# v0_6_2.net
KiCad netlist of a schematic drawn in EAGLE
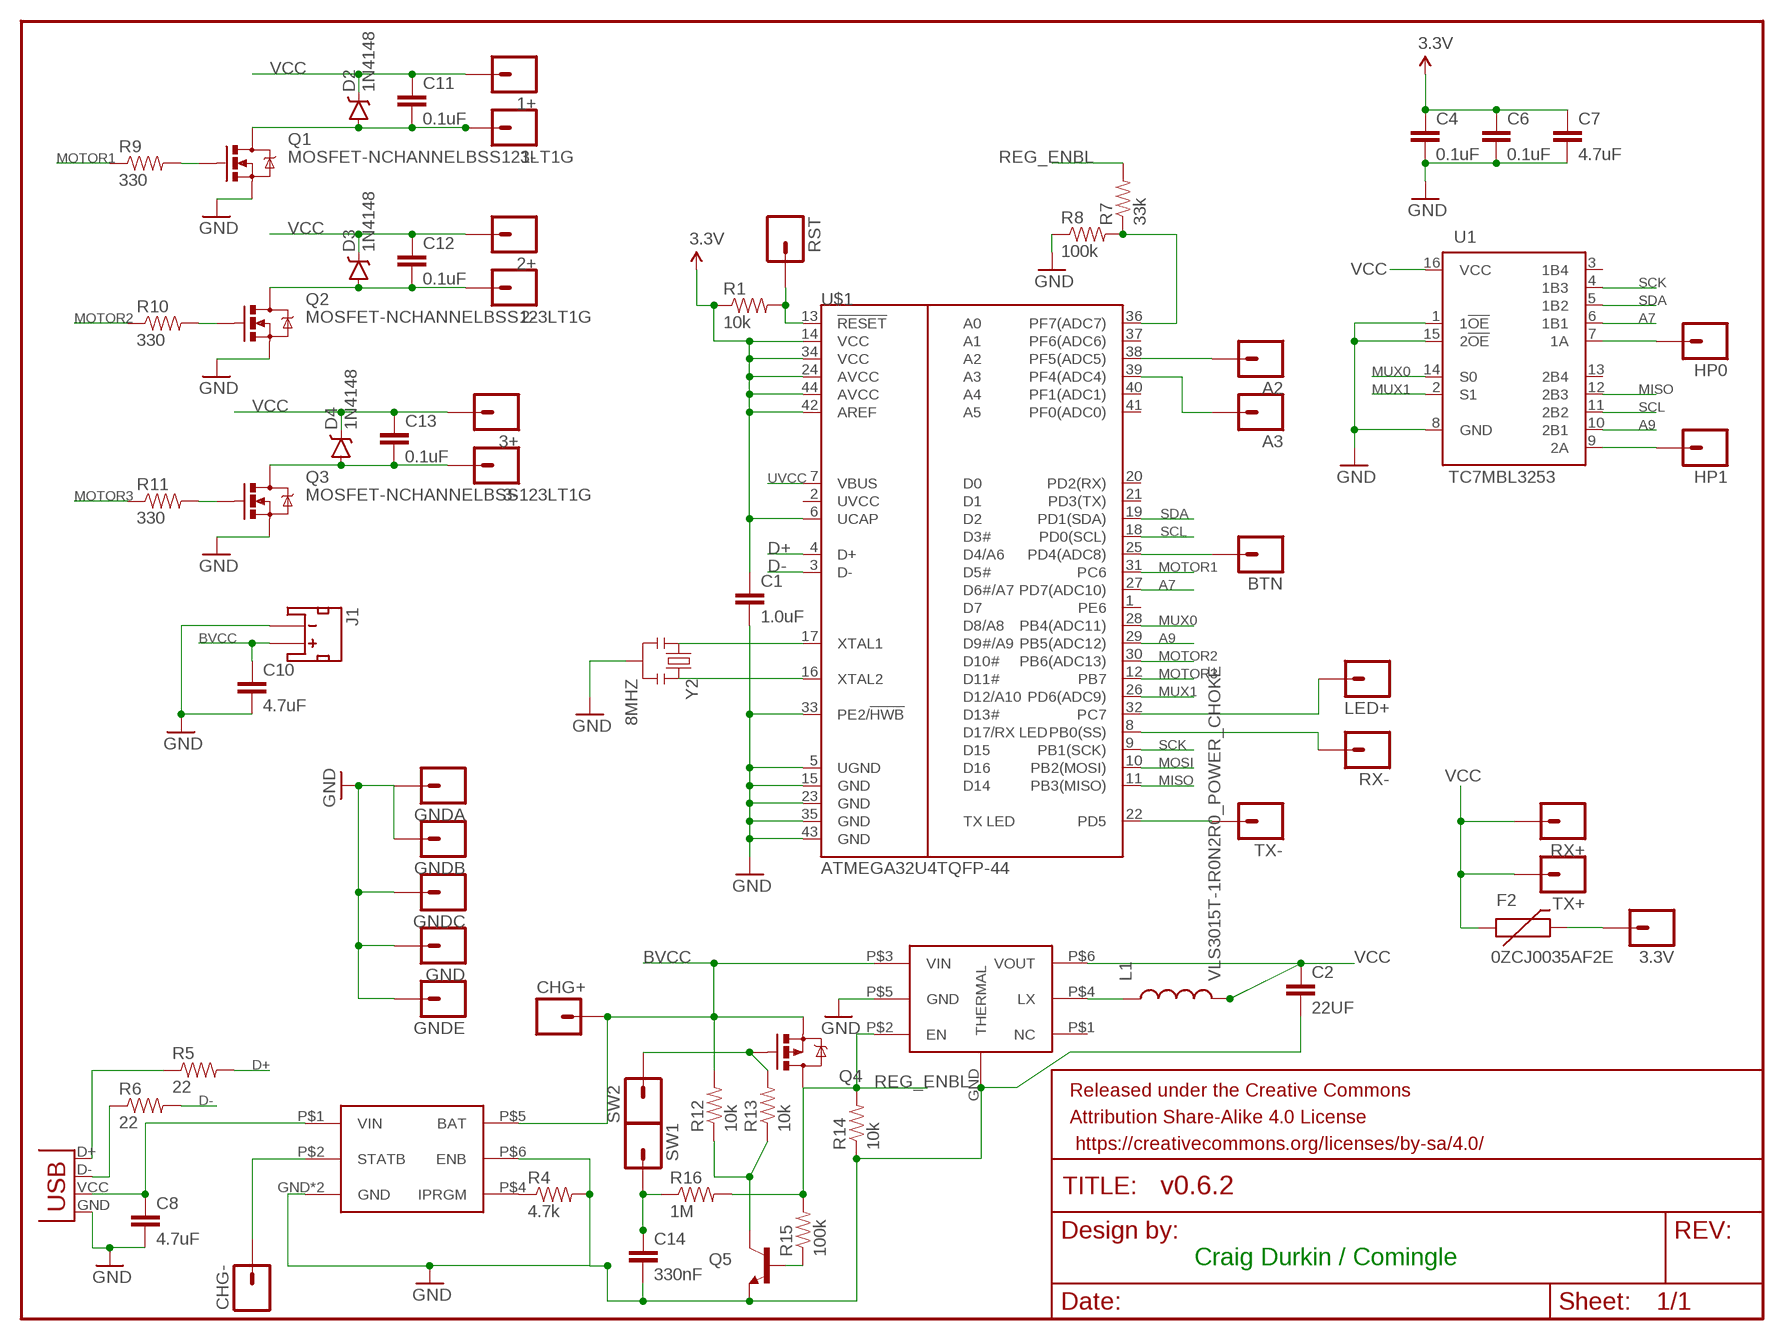
[diagram p0: schematic, sheet 1]

(export (version "E")
  (design (tool "Eeschema 10.0.6"))
  (components
    (comp (ref "1+")
      (value "M01PTH")
      (footprint "eagle-import:1X01")
      (libsource (lib "eagle-import") (part "M01PTH"))
    )
    (comp (ref "1-")
      (value "M01PTH")
      (footprint "eagle-import:1X01")
      (libsource (lib "eagle-import") (part "M01PTH"))
    )
    (comp (ref "2+")
      (value "M01PTH")
      (footprint "eagle-import:1X01")
      (libsource (lib "eagle-import") (part "M01PTH"))
    )
    (comp (ref "2-")
      (value "M01PTH")
      (footprint "eagle-import:1X01")
      (libsource (lib "eagle-import") (part "M01PTH"))
    )
    (comp (ref "3+")
      (value "M01PTH")
      (footprint "eagle-import:1X01")
      (libsource (lib "eagle-import") (part "M01PTH"))
    )
    (comp (ref "3-")
      (value "M01PTH")
      (footprint "eagle-import:1X01")
      (libsource (lib "eagle-import") (part "M01PTH"))
    )
    (comp (ref "3.3V")
      (value "M01PTH")
      (footprint "eagle-import:1X01")
      (libsource (lib "eagle-import") (part "M01PTH"))
    )
    (comp (ref "A2")
      (value "M01PTH")
      (footprint "eagle-import:1X01")
      (libsource (lib "eagle-import") (part "M01PTH"))
    )
    (comp (ref "A3")
      (value "M01PTH")
      (footprint "eagle-import:1X01")
      (libsource (lib "eagle-import") (part "M01PTH"))
    )
    (comp (ref "BTN")
      (value "M01PTH")
      (footprint "eagle-import:1X01")
      (libsource (lib "eagle-import") (part "M01PTH"))
    )
    (comp (ref "C1")
      (value "1.0uF")
      (footprint "eagle-import:0603-CAP")
      (libsource (lib "eagle-import") (part "CAP0603-CAP"))
    )
    (comp (ref "C2")
      (value "22UF")
      (footprint "eagle-import:0805")
      (libsource (lib "eagle-import") (part "v0.4.6_CAP0805"))
    )
    (comp (ref "C4")
      (value "0.1uF")
      (footprint "eagle-import:0603-CAP")
      (libsource (lib "eagle-import") (part "SparkFun-Passives_CAP0603-CAP"))
    )
    (comp (ref "C6")
      (value "0.1uF")
      (footprint "eagle-import:0603-CAP")
      (libsource (lib "eagle-import") (part "SparkFun-Passives_CAP0603-CAP"))
    )
    (comp (ref "C7")
      (value "4.7uF")
      (footprint "eagle-import:0603-CAP")
      (libsource (lib "eagle-import") (part "SparkFun-Passives_CAP0603-CAP"))
    )
    (comp (ref "C8")
      (value "4.7uF")
      (footprint "eagle-import:0603-CAP")
      (libsource (lib "eagle-import") (part "SparkFun-Passives_CAP0603-CAP"))
    )
    (comp (ref "C10")
      (value "4.7uF")
      (footprint "eagle-import:0603-CAP")
      (libsource (lib "eagle-import") (part "SparkFun-Passives_CAP0603-CAP"))
    )
    (comp (ref "C11")
      (value "0.1uF")
      (footprint "eagle-import:0603-CAP")
      (libsource (lib "eagle-import") (part "CAP0603-CAP"))
    )
    (comp (ref "C12")
      (value "0.1uF")
      (footprint "eagle-import:0603-CAP")
      (libsource (lib "eagle-import") (part "CAP0603-CAP"))
    )
    (comp (ref "C13")
      (value "0.1uF")
      (footprint "eagle-import:0603-CAP")
      (libsource (lib "eagle-import") (part "CAP0603-CAP"))
    )
    (comp (ref "C14")
      (value "330nF")
      (footprint "eagle-import:0603-CAP")
      (libsource (lib "eagle-import") (part "CAP0603-CAP"))
    )
    (comp (ref "CHG+")
      (value "M01PTH")
      (footprint "eagle-import:1X01")
      (libsource (lib "eagle-import") (part "M01PTH"))
    )
    (comp (ref "CHG-")
      (value "M01PTH")
      (footprint "eagle-import:1X01")
      (libsource (lib "eagle-import") (part "M01PTH"))
    )
    (comp (ref "D2")
      (value "1N4148")
      (footprint "eagle-import:SOD-323")
      (libsource (lib "eagle-import") (part "BAT20JFILM"))
    )
    (comp (ref "D3")
      (value "1N4148")
      (footprint "eagle-import:SOD-323")
      (libsource (lib "eagle-import") (part "BAT20JFILM"))
    )
    (comp (ref "D4")
      (value "1N4148")
      (footprint "eagle-import:SOD-323")
      (libsource (lib "eagle-import") (part "BAT20JFILM"))
    )
    (comp (ref "F2")
      (value "0ZCJ0035AF2E")
      (footprint "eagle-import:PTC-1206")
      (libsource (lib "eagle-import") (part "PTCSMD"))
    )
    (comp (ref "FRAME1")
      (value "FRAME-LETTER")
      (footprint "eagle-import:CREATIVE_COMMONS")
      (libsource (lib "eagle-import") (part "FRAME-LETTER"))
    )
    (comp (ref "GND")
      (value "M01PTH")
      (footprint "eagle-import:1X01")
      (libsource (lib "eagle-import") (part "M01PTH"))
    )
    (comp (ref "GNDA")
      (value "M01PTH")
      (footprint "eagle-import:1X01")
      (libsource (lib "eagle-import") (part "M01PTH"))
    )
    (comp (ref "GNDB")
      (value "M01PTH")
      (footprint "eagle-import:1X01")
      (libsource (lib "eagle-import") (part "M01PTH"))
    )
    (comp (ref "GNDC")
      (value "M01PTH")
      (footprint "eagle-import:1X01")
      (libsource (lib "eagle-import") (part "M01PTH"))
    )
    (comp (ref "GNDE")
      (value "M01PTH")
      (footprint "eagle-import:1X01")
      (libsource (lib "eagle-import") (part "M01PTH"))
    )
    (comp (ref "HP0")
      (value "M01PTH")
      (footprint "eagle-import:1X01")
      (libsource (lib "eagle-import") (part "M01PTH"))
    )
    (comp (ref "HP1")
      (value "M01PTH")
      (footprint "eagle-import:1X01")
      (libsource (lib "eagle-import") (part "M01PTH"))
    )
    (comp (ref "J1")
      (value "JST_2MM_MALE")
      (footprint "eagle-import:JST-2-SMD")
      (libsource (lib "eagle-import") (part "JST_2MM_MALE"))
    )
    (comp (ref "JP4")
      (value "USBMICROB-GCT-USB3075")
      (footprint "eagle-import:USB-MICROB-GCT-USB3075")
      (libsource (lib "eagle-import") (part "USBMICROB-GCT-USB3075"))
    )
    (comp (ref "L1")
      (value "VLS3015T-1R0N2R0_POWER_CHOKE")
      (footprint "eagle-import:3MM_POWER_CHOKE")
      (libsource (lib "eagle-import") (part "VLS3015T-1R0N2R0_POWER_CHOKE"))
    )
    (comp (ref "LED+")
      (value "M01PTH")
      (footprint "eagle-import:1X01")
      (libsource (lib "eagle-import") (part "M01PTH"))
    )
    (comp (ref "Q1")
      (value "MOSFET-NCHANNELBSS123LT1G")
      (footprint "eagle-import:SOT23-3")
      (libsource (lib "eagle-import") (part "MOSFET-NCHANNELBSS123LT1G"))
    )
    (comp (ref "Q2")
      (value "MOSFET-NCHANNELBSS123LT1G")
      (footprint "eagle-import:SOT23-3")
      (libsource (lib "eagle-import") (part "MOSFET-NCHANNELBSS123LT1G"))
    )
    (comp (ref "Q3")
      (value "MOSFET-NCHANNELBSS123LT1G")
      (footprint "eagle-import:SOT23-3")
      (libsource (lib "eagle-import") (part "MOSFET-NCHANNELBSS123LT1G"))
    )
    (comp (ref "Q4")
      (value "NTS2101PT1G")
      (footprint "eagle-import:SOT323")
      (libsource (lib "eagle-import") (part "MOSFET-PCHANNELSOT323"))
    )
    (comp (ref "Q5")
      (value "MMBT2222A")
      (footprint "eagle-import:SOT23-3")
      (libsource (lib "eagle-import") (part "TRANSISTOR_NPNMMBT2222A"))
    )
    (comp (ref "R1")
      (value "10k")
      (footprint "eagle-import:0603-RES")
      (libsource (lib "eagle-import") (part "RESISTOR0603-RES"))
    )
    (comp (ref "R4")
      (value "4.7k")
      (footprint "eagle-import:0603-RES")
      (libsource (lib "eagle-import") (part "RESISTOR0603-RES"))
    )
    (comp (ref "R5")
      (value "22")
      (footprint "eagle-import:0603-RES")
      (libsource (lib "eagle-import") (part "RESISTOR0603-RES"))
    )
    (comp (ref "R6")
      (value "22")
      (footprint "eagle-import:0603-RES")
      (libsource (lib "eagle-import") (part "RESISTOR0603-RES"))
    )
    (comp (ref "R7")
      (value "33k")
      (footprint "eagle-import:0603-RES")
      (libsource (lib "eagle-import") (part "RESISTOR0603-RES"))
    )
    (comp (ref "R8")
      (value "100k")
      (footprint "eagle-import:0603-RES")
      (libsource (lib "eagle-import") (part "RESISTOR0603-RES"))
    )
    (comp (ref "R9")
      (value "330")
      (footprint "eagle-import:0603-RES")
      (libsource (lib "eagle-import") (part "RESISTOR0603-RES"))
    )
    (comp (ref "R10")
      (value "330")
      (footprint "eagle-import:0603-RES")
      (libsource (lib "eagle-import") (part "RESISTOR0603-RES"))
    )
    (comp (ref "R11")
      (value "330")
      (footprint "eagle-import:0603-RES")
      (libsource (lib "eagle-import") (part "RESISTOR0603-RES"))
    )
    (comp (ref "R12")
      (value "10k")
      (footprint "eagle-import:0603-RES")
      (libsource (lib "eagle-import") (part "RESISTOR0603-RES"))
    )
    (comp (ref "R13")
      (value "10k")
      (footprint "eagle-import:0603-RES")
      (libsource (lib "eagle-import") (part "RESISTOR0603-RES"))
    )
    (comp (ref "R14")
      (value "10k")
      (footprint "eagle-import:0603-RES")
      (libsource (lib "eagle-import") (part "RESISTOR0603-RES"))
    )
    (comp (ref "R15")
      (value "100k")
      (footprint "eagle-import:0603-RES")
      (libsource (lib "eagle-import") (part "RESISTOR0603-RES"))
    )
    (comp (ref "R16")
      (value "1M")
      (footprint "eagle-import:0603-RES")
      (libsource (lib "eagle-import") (part "RESISTOR0603-RES"))
    )
    (comp (ref "RST")
      (value "M01PTH")
      (footprint "eagle-import:1X01")
      (libsource (lib "eagle-import") (part "M01PTH"))
    )
    (comp (ref "RX+")
      (value "M01PTH")
      (footprint "eagle-import:1X01")
      (libsource (lib "eagle-import") (part "M01PTH"))
    )
    (comp (ref "RX-")
      (value "M01PTH")
      (footprint "eagle-import:1X01")
      (libsource (lib "eagle-import") (part "M01PTH"))
    )
    (comp (ref "SW1")
      (value "M01PTH")
      (footprint "eagle-import:1X01")
      (libsource (lib "eagle-import") (part "M01PTH"))
    )
    (comp (ref "SW2")
      (value "M01PTH")
      (footprint "eagle-import:1X01")
      (libsource (lib "eagle-import") (part "M01PTH"))
    )
    (comp (ref "TX+")
      (value "M01PTH")
      (footprint "eagle-import:1X01")
      (libsource (lib "eagle-import") (part "M01PTH"))
    )
    (comp (ref "TX-")
      (value "M01PTH")
      (footprint "eagle-import:1X01")
      (libsource (lib "eagle-import") (part "M01PTH"))
    )
    (comp (ref "U$1")
      (value "ATMEGA32U4TQFP-44")
      (footprint "eagle-import:TQFP44")
      (libsource (lib "eagle-import") (part "ATMEGA32U4TQFP-44"))
    )
    (comp (ref "U$3")
      (value "SC189")
      (footprint "eagle-import:MLPD-UT6")
      (libsource (lib "eagle-import") (part "SC189"))
    )
    (comp (ref "U$4")
      (value "SC810")
      (footprint "eagle-import:MLPD-UT6")
      (libsource (lib "eagle-import") (part "SC810"))
    )
    (comp (ref "U1")
      (value "TC7MBL3253")
      (footprint "eagle-import:SSOP16")
      (libsource (lib "eagle-import") (part "TC7MBL3253"))
    )
    (comp (ref "Y2")
      (value "8MHZ")
      (footprint "eagle-import:RESONATOR-SMD")
      (libsource (lib "eagle-import") (part "RESONATOR8MHZ"))
    )
  )
  (nets
    (net (code "1") (name "/A7") (class "Default")
      (node (ref "U$1") (pin "27") (pinfunction "PD7(ADC10)_27") (pintype "bidirectional"))
      (node (ref "U1") (pin "6") (pinfunction "1B1_6") (pintype "bidirectional"))
    )
    (net (code "2") (name "/A9") (class "Default")
      (node (ref "U$1") (pin "29") (pinfunction "PB5(ADC12)_29") (pintype "bidirectional"))
      (node (ref "U1") (pin "10") (pinfunction "2B1_10") (pintype "bidirectional"))
    )
    (net (code "3") (name "/BVCC") (class "Default")
      (node (ref "C10") (pin "1") (pinfunction "1_1") (pintype "passive"))
      (node (ref "CHG+") (pin "1") (pinfunction "1_1") (pintype "passive"))
      (node (ref "J1") (pin "2") (pinfunction "+_2") (pintype "bidirectional"))
      (node (ref "Q4") (pin "2") (pinfunction "S_2") (pintype "passive"))
      (node (ref "R12") (pin "2") (pinfunction "2_2") (pintype "passive"))
      (node (ref "U$3") (pin "P$3") (pinfunction "VIN_P$3") (pintype "power_in"))
      (node (ref "U$4") (pin "P$5") (pinfunction "BAT_P$5") (pintype "output"))
    )
    (net (code "4") (name "/D+") (class "Default")
      (node (ref "R5") (pin "2") (pinfunction "2_2") (pintype "passive"))
      (node (ref "U$1") (pin "4") (pinfunction "D+_4") (pintype "bidirectional"))
    )
    (net (code "5") (name "/D-") (class "Default")
      (node (ref "R6") (pin "2") (pinfunction "2_2") (pintype "passive"))
      (node (ref "U$1") (pin "3") (pinfunction "D-_3") (pintype "bidirectional"))
    )
    (net (code "6") (name "/MISO") (class "Default")
      (node (ref "U$1") (pin "11") (pinfunction "PB3(MISO)_11") (pintype "bidirectional"))
      (node (ref "U1") (pin "12") (pinfunction "2B3_12") (pintype "bidirectional"))
    )
    (net (code "7") (name "/MOSI") (class "Default")
      (node (ref "U$1") (pin "10") (pinfunction "PB2(MOSI)_10") (pintype "bidirectional"))
    )
    (net (code "8") (name "/MOTOR1") (class "Default")
      (node (ref "R9") (pin "1") (pinfunction "1_1") (pintype "passive"))
      (node (ref "U$1") (pin "31") (pinfunction "PC6_31") (pintype "bidirectional"))
    )
    (net (code "9") (name "/MOTOR2") (class "Default")
      (node (ref "R10") (pin "1") (pinfunction "1_1") (pintype "passive"))
      (node (ref "U$1") (pin "30") (pinfunction "PB6(ADC13)_30") (pintype "bidirectional"))
    )
    (net (code "10") (name "/MOTOR3") (class "Default")
      (node (ref "R11") (pin "1") (pinfunction "1_1") (pintype "passive"))
      (node (ref "U$1") (pin "12") (pinfunction "PB7_12") (pintype "bidirectional"))
    )
    (net (code "11") (name "/MUX0") (class "Default")
      (node (ref "U$1") (pin "28") (pinfunction "PB4(ADC11)_28") (pintype "bidirectional"))
      (node (ref "U1") (pin "14") (pinfunction "S0_14") (pintype "bidirectional"))
    )
    (net (code "12") (name "/MUX1") (class "Default")
      (node (ref "U$1") (pin "26") (pinfunction "PD6(ADC9)_26") (pintype "bidirectional"))
      (node (ref "U1") (pin "2") (pinfunction "S1_2") (pintype "bidirectional"))
    )
    (net (code "13") (name "/REG_ENBL") (class "Default")
      (node (ref "Q4") (pin "3") (pinfunction "D_3") (pintype "passive"))
      (node (ref "R14") (pin "2") (pinfunction "2_2") (pintype "passive"))
      (node (ref "R15") (pin "2") (pinfunction "2_2") (pintype "passive"))
      (node (ref "R16") (pin "2") (pinfunction "2_2") (pintype "passive"))
      (node (ref "R7") (pin "2") (pinfunction "2_2") (pintype "passive"))
      (node (ref "U$3") (pin "P$2") (pinfunction "EN_P$2") (pintype "input"))
    )
    (net (code "14") (name "/SCK") (class "Default")
      (node (ref "U$1") (pin "9") (pinfunction "PB1(SCK)_9") (pintype "bidirectional"))
      (node (ref "U1") (pin "4") (pinfunction "1B3_4") (pintype "bidirectional"))
    )
    (net (code "15") (name "/SCL") (class "Default")
      (node (ref "U$1") (pin "18") (pinfunction "PD0(SCL)_18") (pintype "bidirectional"))
      (node (ref "U1") (pin "11") (pinfunction "2B2_11") (pintype "bidirectional"))
    )
    (net (code "16") (name "/SDA") (class "Default")
      (node (ref "U$1") (pin "19") (pinfunction "PD1(SDA)_19") (pintype "bidirectional"))
      (node (ref "U1") (pin "5") (pinfunction "1B2_5") (pintype "bidirectional"))
    )
    (net (code "17") (name "/UVCC") (class "Default")
      (node (ref "C8") (pin "1") (pinfunction "1_1") (pintype "passive"))
      (node (ref "JP4") (pin "VCC") (pinfunction "VBUS_VCC") (pintype "bidirectional"))
      (node (ref "U$1") (pin "7") (pinfunction "VBUS_7") (pintype "bidirectional"))
      (node (ref "U$4") (pin "P$1") (pinfunction "VIN_P$1") (pintype "power_in"))
    )
    (net (code "18") (name "3.3V") (class "Default")
      (node (ref "1+") (pin "1") (pinfunction "1_1") (pintype "passive"))
      (node (ref "2+") (pin "1") (pinfunction "1_1") (pintype "passive"))
      (node (ref "3+") (pin "1") (pinfunction "1_1") (pintype "passive"))
      (node (ref "C1") (pin "1") (pinfunction "1_1") (pintype "passive"))
      (node (ref "C11") (pin "1") (pinfunction "1_1") (pintype "passive"))
      (node (ref "C12") (pin "1") (pinfunction "1_1") (pintype "passive"))
      (node (ref "C13") (pin "1") (pinfunction "1_1") (pintype "passive"))
      (node (ref "C2") (pin "1") (pinfunction "1_1") (pintype "passive"))
      (node (ref "C4") (pin "1") (pinfunction "1_1") (pintype "passive"))
      (node (ref "C6") (pin "1") (pinfunction "1_1") (pintype "passive"))
      (node (ref "C7") (pin "1") (pinfunction "1_1") (pintype "passive"))
      (node (ref "D2") (pin "C") (pinfunction "C_C") (pintype "passive"))
      (node (ref "D3") (pin "C") (pinfunction "C_C") (pintype "passive"))
      (node (ref "D4") (pin "C") (pinfunction "C_C") (pintype "passive"))
      (node (ref "F2") (pin "1") (pinfunction "1_1") (pintype "bidirectional"))
      (node (ref "L1") (pin "2") (pinfunction "2_2") (pintype "passive"))
      (node (ref "R1") (pin "1") (pinfunction "1_1") (pintype "passive"))
      (node (ref "RX+") (pin "1") (pinfunction "1_1") (pintype "passive"))
      (node (ref "TX+") (pin "1") (pinfunction "1_1") (pintype "passive"))
      (node (ref "U$1") (pin "14") (pinfunction "VCC_14") (pintype "bidirectional"))
      (node (ref "U$1") (pin "24") (pinfunction "AVCC_24") (pintype "bidirectional"))
      (node (ref "U$1") (pin "34") (pinfunction "VCC_34") (pintype "bidirectional"))
      (node (ref "U$1") (pin "42") (pinfunction "AREF_42") (pintype "bidirectional"))
      (node (ref "U$1") (pin "44") (pinfunction "AVCC_44") (pintype "bidirectional"))
      (node (ref "U$1") (pin "6") (pinfunction "UCAP_6") (pintype "bidirectional"))
      (node (ref "U$3") (pin "P$6") (pinfunction "VOUT_P$6") (pintype "output"))
      (node (ref "U1") (pin "16") (pinfunction "VCC_16") (pintype "power_in"))
    )
    (net (code "19") (name "GND") (class "Default")
      (node (ref "C1") (pin "2") (pinfunction "2_2") (pintype "passive"))
      (node (ref "C10") (pin "2") (pinfunction "2_2") (pintype "passive"))
      (node (ref "C14") (pin "2") (pinfunction "2_2") (pintype "passive"))
      (node (ref "C2") (pin "2") (pinfunction "2_2") (pintype "passive"))
      (node (ref "C4") (pin "2") (pinfunction "2_2") (pintype "passive"))
      (node (ref "C6") (pin "2") (pinfunction "2_2") (pintype "passive"))
      (node (ref "C7") (pin "2") (pinfunction "2_2") (pintype "passive"))
      (node (ref "C8") (pin "2") (pinfunction "2_2") (pintype "passive"))
      (node (ref "GND") (pin "1") (pinfunction "1_1") (pintype "passive"))
      (node (ref "GNDA") (pin "1") (pinfunction "1_1") (pintype "passive"))
      (node (ref "GNDB") (pin "1") (pinfunction "1_1") (pintype "passive"))
      (node (ref "GNDC") (pin "1") (pinfunction "1_1") (pintype "passive"))
      (node (ref "GNDE") (pin "1") (pinfunction "1_1") (pintype "passive"))
      (node (ref "J1") (pin "1") (pinfunction "-_1") (pintype "bidirectional"))
      (node (ref "JP4") (pin "GND") (pinfunction "GND_GND") (pintype "bidirectional"))
      (node (ref "Q1") (pin "2") (pinfunction "S_2") (pintype "passive"))
      (node (ref "Q2") (pin "2") (pinfunction "S_2") (pintype "passive"))
      (node (ref "Q3") (pin "2") (pinfunction "S_2") (pintype "passive"))
      (node (ref "Q5") (pin "2") (pinfunction "E_2") (pintype "passive"))
      (node (ref "R14") (pin "1") (pinfunction "1_1") (pintype "passive"))
      (node (ref "R4") (pin "2") (pinfunction "2_2") (pintype "passive"))
      (node (ref "R8") (pin "1") (pinfunction "1_1") (pintype "passive"))
      (node (ref "U$1") (pin "15") (pinfunction "GND_15") (pintype "bidirectional"))
      (node (ref "U$1") (pin "23") (pinfunction "GND_23") (pintype "bidirectional"))
      (node (ref "U$1") (pin "33") (pinfunction "PE2/~{HWB}_33") (pintype "bidirectional"))
      (node (ref "U$1") (pin "35") (pinfunction "GND_35") (pintype "bidirectional"))
      (node (ref "U$1") (pin "43") (pinfunction "GND_43") (pintype "bidirectional"))
      (node (ref "U$1") (pin "5") (pinfunction "UGND_5") (pintype "bidirectional"))
      (node (ref "U$3") (pin "GND") (pinfunction "THERMAL_GND") (pintype "power_in"))
      (node (ref "U$3") (pin "P$5") (pinfunction "GND_P$5") (pintype "power_in"))
      (node (ref "U$4") (pin "GND") (pinfunction "GND_GND") (pintype "power_in"))
      (node (ref "U$4") (pin "P$3") (pinfunction "GND_P$3") (pintype "power_in"))
      (node (ref "U$4") (pin "P$6") (pinfunction "ENB_P$6") (pintype "bidirectional"))
      (node (ref "U1") (pin "1") (pinfunction "1~{OE}_1") (pintype "input"))
      (node (ref "U1") (pin "15") (pinfunction "2~{OE}_15") (pintype "input"))
      (node (ref "U1") (pin "8") (pinfunction "GND_8") (pintype "power_in"))
      (node (ref "Y2") (pin "2") (pinfunction "2_2") (pintype "passive"))
    )
    (net (code "20") (name "Net-(3.3V-Pad1)") (class "Default")
      (node (ref "3.3V") (pin "1") (pinfunction "1_1") (pintype "passive"))
      (node (ref "F2") (pin "2") (pinfunction "2_2") (pintype "bidirectional"))
    )
    (net (code "21") (name "Net-(C14-Pad1)") (class "Default")
      (node (ref "C14") (pin "1") (pinfunction "1_1") (pintype "passive"))
      (node (ref "R16") (pin "1") (pinfunction "1_1") (pintype "passive"))
      (node (ref "SW1") (pin "1") (pinfunction "1_1") (pintype "passive"))
    )
    (net (code "22") (name "Net-(JP4-PadD+)") (class "Default")
      (node (ref "JP4") (pin "D+") (pinfunction "D+_D+") (pintype "bidirectional"))
      (node (ref "R5") (pin "1") (pinfunction "1_1") (pintype "passive"))
    )
    (net (code "23") (name "Net-(JP4-PadD-)") (class "Default")
      (node (ref "JP4") (pin "D-") (pinfunction "D-_D-") (pintype "bidirectional"))
      (node (ref "R6") (pin "1") (pinfunction "1_1") (pintype "passive"))
    )
    (net (code "24") (name "Net-(Q1-D)") (class "Default")
      (node (ref "1-") (pin "1") (pinfunction "1_1") (pintype "passive"))
      (node (ref "C11") (pin "2") (pinfunction "2_2") (pintype "passive"))
      (node (ref "D2") (pin "A") (pinfunction "A_A") (pintype "passive"))
      (node (ref "Q1") (pin "3") (pinfunction "D_3") (pintype "passive"))
    )
    (net (code "25") (name "Net-(Q1-G)") (class "Default")
      (node (ref "Q1") (pin "1") (pinfunction "G_1") (pintype "passive"))
      (node (ref "R9") (pin "2") (pinfunction "2_2") (pintype "passive"))
    )
    (net (code "26") (name "Net-(Q2-D)") (class "Default")
      (node (ref "2-") (pin "1") (pinfunction "1_1") (pintype "passive"))
      (node (ref "C12") (pin "2") (pinfunction "2_2") (pintype "passive"))
      (node (ref "D3") (pin "A") (pinfunction "A_A") (pintype "passive"))
      (node (ref "Q2") (pin "3") (pinfunction "D_3") (pintype "passive"))
    )
    (net (code "27") (name "Net-(Q2-G)") (class "Default")
      (node (ref "Q2") (pin "1") (pinfunction "G_1") (pintype "passive"))
      (node (ref "R10") (pin "2") (pinfunction "2_2") (pintype "passive"))
    )
    (net (code "28") (name "Net-(Q3-D)") (class "Default")
      (node (ref "3-") (pin "1") (pinfunction "1_1") (pintype "passive"))
      (node (ref "C13") (pin "2") (pinfunction "2_2") (pintype "passive"))
      (node (ref "D4") (pin "A") (pinfunction "A_A") (pintype "passive"))
      (node (ref "Q3") (pin "3") (pinfunction "D_3") (pintype "passive"))
    )
    (net (code "29") (name "Net-(Q3-G)") (class "Default")
      (node (ref "Q3") (pin "1") (pinfunction "G_1") (pintype "passive"))
      (node (ref "R11") (pin "2") (pinfunction "2_2") (pintype "passive"))
    )
    (net (code "30") (name "Net-(Q4-G)") (class "Default")
      (node (ref "Q4") (pin "1") (pinfunction "G_1") (pintype "passive"))
      (node (ref "R13") (pin "2") (pinfunction "2_2") (pintype "passive"))
      (node (ref "SW2") (pin "1") (pinfunction "1_1") (pintype "passive"))
    )
    (net (code "31") (name "Net-(Q5-B)") (class "Default")
      (node (ref "Q5") (pin "1") (pinfunction "B_1") (pintype "passive"))
      (node (ref "R15") (pin "1") (pinfunction "1_1") (pintype "passive"))
    )
    (net (code "32") (name "Net-(Q5-C)") (class "Default")
      (node (ref "Q5") (pin "3") (pinfunction "C_3") (pintype "passive"))
      (node (ref "R12") (pin "1") (pinfunction "1_1") (pintype "passive"))
      (node (ref "R13") (pin "1") (pinfunction "1_1") (pintype "passive"))
    )
    (net (code "33") (name "Net-(U$1-PB0(SS))") (class "Default")
      (node (ref "RX-") (pin "1") (pinfunction "1_1") (pintype "passive"))
      (node (ref "U$1") (pin "8") (pinfunction "PB0(SS)_8") (pintype "bidirectional"))
    )
    (net (code "34") (name "Net-(U$1-PC7)") (class "Default")
      (node (ref "LED+") (pin "1") (pinfunction "1_1") (pintype "passive"))
      (node (ref "U$1") (pin "32") (pinfunction "PC7_32") (pintype "bidirectional"))
    )
    (net (code "35") (name "Net-(U$1-PD4(ADC8))") (class "Default")
      (node (ref "BTN") (pin "1") (pinfunction "1_1") (pintype "passive"))
      (node (ref "U$1") (pin "25") (pinfunction "PD4(ADC8)_25") (pintype "bidirectional"))
    )
    (net (code "36") (name "Net-(U$1-PD5)") (class "Default")
      (node (ref "TX-") (pin "1") (pinfunction "1_1") (pintype "passive"))
      (node (ref "U$1") (pin "22") (pinfunction "PD5_22") (pintype "bidirectional"))
    )
    (net (code "37") (name "Net-(U$1-PF4(ADC4))") (class "Default")
      (node (ref "A3") (pin "1") (pinfunction "1_1") (pintype "passive"))
      (node (ref "U$1") (pin "39") (pinfunction "PF4(ADC4)_39") (pintype "bidirectional"))
    )
    (net (code "38") (name "Net-(U$1-PF5(ADC5))") (class "Default")
      (node (ref "A2") (pin "1") (pinfunction "1_1") (pintype "passive"))
      (node (ref "U$1") (pin "38") (pinfunction "PF5(ADC5)_38") (pintype "bidirectional"))
    )
    (net (code "39") (name "Net-(U$1-PF7(ADC7))") (class "Default")
      (node (ref "R7") (pin "1") (pinfunction "1_1") (pintype "passive"))
      (node (ref "R8") (pin "2") (pinfunction "2_2") (pintype "passive"))
      (node (ref "U$1") (pin "36") (pinfunction "PF7(ADC7)_36") (pintype "bidirectional"))
    )
    (net (code "40") (name "Net-(U$1-XTAL1)") (class "Default")
      (node (ref "U$1") (pin "17") (pinfunction "XTAL1_17") (pintype "bidirectional"))
      (node (ref "Y2") (pin "1") (pinfunction "1_1") (pintype "passive"))
    )
    (net (code "41") (name "Net-(U$1-XTAL2)") (class "Default")
      (node (ref "U$1") (pin "16") (pinfunction "XTAL2_16") (pintype "bidirectional"))
      (node (ref "Y2") (pin "3") (pinfunction "3_3") (pintype "passive"))
    )
    (net (code "42") (name "Net-(U$1-~{RESET})") (class "Default")
      (node (ref "R1") (pin "2") (pinfunction "2_2") (pintype "passive"))
      (node (ref "RST") (pin "1") (pinfunction "1_1") (pintype "passive"))
      (node (ref "U$1") (pin "13") (pinfunction "~{RESET}_13") (pintype "bidirectional"))
    )
    (net (code "43") (name "Net-(U$3-LX)") (class "Default")
      (node (ref "L1") (pin "1") (pinfunction "1_1") (pintype "passive"))
      (node (ref "U$3") (pin "P$4") (pinfunction "LX_P$4") (pintype "passive"))
    )
    (net (code "44") (name "Net-(U$4-IPRGM)") (class "Default")
      (node (ref "R4") (pin "1") (pinfunction "1_1") (pintype "passive"))
      (node (ref "U$4") (pin "P$4") (pinfunction "IPRGM_P$4") (pintype "bidirectional"))
    )
    (net (code "45") (name "Net-(U$4-STATB)") (class "Default")
      (node (ref "CHG-") (pin "1") (pinfunction "1_1") (pintype "passive"))
      (node (ref "U$4") (pin "P$2") (pinfunction "STATB_P$2") (pintype "bidirectional"))
    )
    (net (code "46") (name "Net-(U1-1A)") (class "Default")
      (node (ref "HP0") (pin "1") (pinfunction "1_1") (pintype "passive"))
      (node (ref "U1") (pin "7") (pinfunction "1A_7") (pintype "bidirectional"))
    )
    (net (code "47") (name "Net-(U1-2A)") (class "Default")
      (node (ref "HP1") (pin "1") (pinfunction "1_1") (pintype "passive"))
      (node (ref "U1") (pin "9") (pinfunction "2A_9") (pintype "bidirectional"))
    )
    (net (code "48") (name "unconnected-(J1-PAD1-PadNC1)") (class "Default")
      (node (ref "J1") (pin "NC1") (pinfunction "PAD1_NC1") (pintype "bidirectional"))
    )
    (net (code "49") (name "unconnected-(J1-PAD2-PadNC2)") (class "Default")
      (node (ref "J1") (pin "NC2") (pinfunction "PAD2_NC2") (pintype "bidirectional"))
    )
    (net (code "50") (name "unconnected-(U$1-PD2(RX)-Pad20)") (class "Default")
      (node (ref "U$1") (pin "20") (pinfunction "PD2(RX)_20") (pintype "bidirectional"))
    )
    (net (code "51") (name "unconnected-(U$1-PD3(TX)-Pad21)") (class "Default")
      (node (ref "U$1") (pin "21") (pinfunction "PD3(TX)_21") (pintype "bidirectional"))
    )
    (net (code "52") (name "unconnected-(U$1-PE6-Pad1)") (class "Default")
      (node (ref "U$1") (pin "1") (pinfunction "PE6_1") (pintype "bidirectional"))
    )
    (net (code "53") (name "unconnected-(U$1-PF0(ADC0)-Pad41)") (class "Default")
      (node (ref "U$1") (pin "41") (pinfunction "PF0(ADC0)_41") (pintype "bidirectional"))
    )
    (net (code "54") (name "unconnected-(U$1-PF1(ADC1)-Pad40)") (class "Default")
      (node (ref "U$1") (pin "40") (pinfunction "PF1(ADC1)_40") (pintype "bidirectional"))
    )
    (net (code "55") (name "unconnected-(U$1-PF6(ADC6)-Pad37)") (class "Default")
      (node (ref "U$1") (pin "37") (pinfunction "PF6(ADC6)_37") (pintype "bidirectional"))
    )
    (net (code "56") (name "unconnected-(U$1-UVCC-Pad2)") (class "Default")
      (node (ref "U$1") (pin "2") (pinfunction "UVCC_2") (pintype "bidirectional"))
    )
    (net (code "57") (name "unconnected-(U$3-NC-PadP$1)") (class "Default")
      (node (ref "U$3") (pin "P$1") (pinfunction "NC_P$1") (pintype "no_connect"))
    )
    (net (code "58") (name "unconnected-(U1-1B4-Pad3)") (class "Default")
      (node (ref "U1") (pin "3") (pinfunction "1B4_3") (pintype "bidirectional"))
    )
    (net (code "59") (name "unconnected-(U1-2B4-Pad13)") (class "Default")
      (node (ref "U1") (pin "13") (pinfunction "2B4_13") (pintype "bidirectional"))
    )
  )
)
